# Q24brakelightsch.net
KiCad netlist of a schematic drawn in Altium Designer
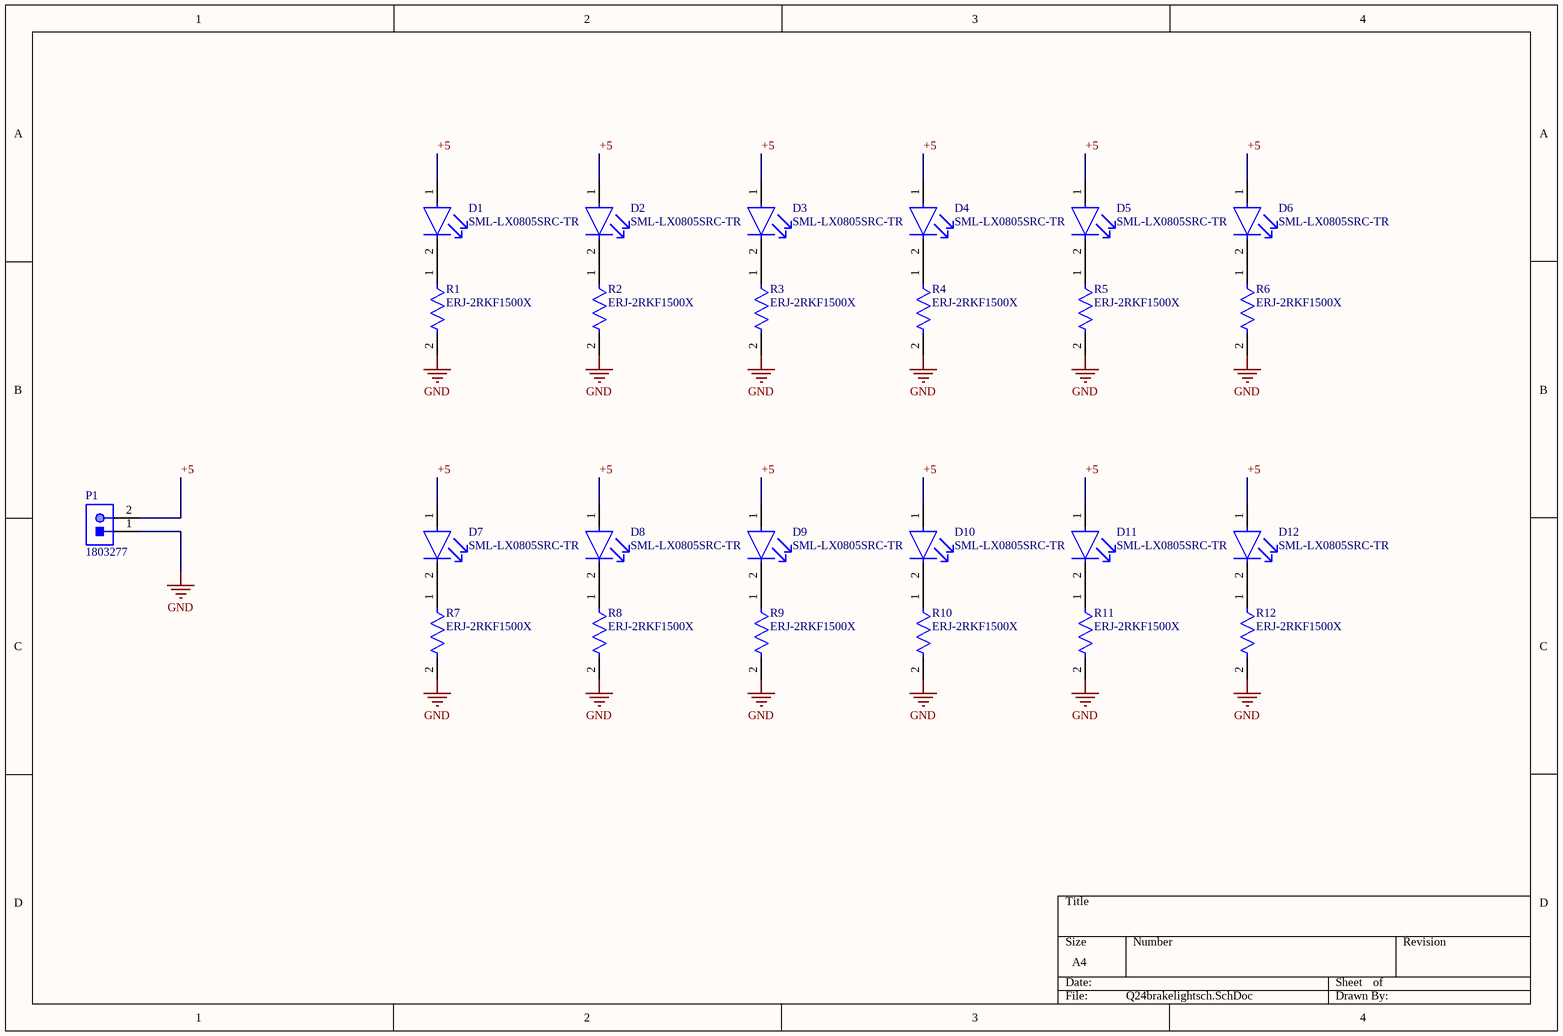
[diagram p0: Q24brakelightsch.SchDoc]

(export (version "E")
  (design (tool "Eeschema 10.0.6"))
  (components
    (comp (ref "D1")
      (value "SML-LX0805SRC-TR")
      (footprint "FP-SML-LX0805SRC-TR-MFG")
      (description "LED RED CLEAR SMD")
      (libsource (lib "Altium Content Vault") (part "ab1c01a81903e929fc6c44469aada92"))
    )
    (comp (ref "D2")
      (value "SML-LX0805SRC-TR")
      (footprint "FP-SML-LX0805SRC-TR-MFG")
      (description "LED RED CLEAR SMD")
      (libsource (lib "Altium Content Vault") (part "ab1c01a81903e929fc6c44469aada92"))
    )
    (comp (ref "D3")
      (value "SML-LX0805SRC-TR")
      (footprint "FP-SML-LX0805SRC-TR-MFG")
      (description "LED RED CLEAR SMD")
      (libsource (lib "Altium Content Vault") (part "ab1c01a81903e929fc6c44469aada92"))
    )
    (comp (ref "D4")
      (value "SML-LX0805SRC-TR")
      (footprint "FP-SML-LX0805SRC-TR-MFG")
      (description "LED RED CLEAR SMD")
      (libsource (lib "Altium Content Vault") (part "ab1c01a81903e929fc6c44469aada92"))
    )
    (comp (ref "D5")
      (value "SML-LX0805SRC-TR")
      (footprint "FP-SML-LX0805SRC-TR-MFG")
      (description "LED RED CLEAR SMD")
      (libsource (lib "Altium Content Vault") (part "ab1c01a81903e929fc6c44469aada92"))
    )
    (comp (ref "D6")
      (value "SML-LX0805SRC-TR")
      (footprint "FP-SML-LX0805SRC-TR-MFG")
      (description "LED RED CLEAR SMD")
      (libsource (lib "Altium Content Vault") (part "ab1c01a81903e929fc6c44469aada92"))
    )
    (comp (ref "D7")
      (value "SML-LX0805SRC-TR")
      (footprint "FP-SML-LX0805SRC-TR-MFG")
      (description "LED RED CLEAR SMD")
      (libsource (lib "Altium Content Vault") (part "ab1c01a81903e929fc6c44469aada92"))
    )
    (comp (ref "D8")
      (value "SML-LX0805SRC-TR")
      (footprint "FP-SML-LX0805SRC-TR-MFG")
      (description "LED RED CLEAR SMD")
      (libsource (lib "Altium Content Vault") (part "ab1c01a81903e929fc6c44469aada92"))
    )
    (comp (ref "D9")
      (value "SML-LX0805SRC-TR")
      (footprint "FP-SML-LX0805SRC-TR-MFG")
      (description "LED RED CLEAR SMD")
      (libsource (lib "Altium Content Vault") (part "ab1c01a81903e929fc6c44469aada92"))
    )
    (comp (ref "D10")
      (value "SML-LX0805SRC-TR")
      (footprint "FP-SML-LX0805SRC-TR-MFG")
      (description "LED RED CLEAR SMD")
      (libsource (lib "Altium Content Vault") (part "ab1c01a81903e929fc6c44469aada92"))
    )
    (comp (ref "D11")
      (value "SML-LX0805SRC-TR")
      (footprint "FP-SML-LX0805SRC-TR-MFG")
      (description "LED RED CLEAR SMD")
      (libsource (lib "Altium Content Vault") (part "ab1c01a81903e929fc6c44469aada92"))
    )
    (comp (ref "D12")
      (value "SML-LX0805SRC-TR")
      (footprint "FP-SML-LX0805SRC-TR-MFG")
      (description "LED RED CLEAR SMD")
      (libsource (lib "Altium Content Vault") (part "ab1c01a81903e929fc6c44469aada92"))
    )
    (comp (ref "P1")
      (value "1803277")
      (footprint "PHOE-1803277_V")
      (description "Male Header, Pitch 3.81 mm, 1 x 2 Position, Height 7.25 mm, Tail Length 3.4 mm, RoHS, Bulk")
      (fields (field (name "MANUFACTURER") "Phoenix Contact"))
      (libsource (lib "Americas- FSAE- Queens University") (part "CN-1P-M-R2"))
    )
    (comp (ref "R1")
      (value "ERJ-2RKF1500X")
      (footprint "FP-ERJ2RK-IPC_A")
      (description "RES SMD 150 OHM 1% 1/10W 0402")
      (fields (field (name "TOLERANCE") "1%"))
      (libsource (lib "Altium Content Vault") (part "1029c3af85768c4190bb7ad29bc67b5"))
    )
    (comp (ref "R2")
      (value "ERJ-2RKF1500X")
      (footprint "FP-ERJ2RK-IPC_A")
      (description "RES SMD 150 OHM 1% 1/10W 0402")
      (fields (field (name "TOLERANCE") "1%"))
      (libsource (lib "Altium Content Vault") (part "1029c3af85768c4190bb7ad29bc67b5"))
    )
    (comp (ref "R3")
      (value "ERJ-2RKF1500X")
      (footprint "FP-ERJ2RK-IPC_A")
      (description "RES SMD 150 OHM 1% 1/10W 0402")
      (fields (field (name "TOLERANCE") "1%"))
      (libsource (lib "Altium Content Vault") (part "1029c3af85768c4190bb7ad29bc67b5"))
    )
    (comp (ref "R4")
      (value "ERJ-2RKF1500X")
      (footprint "FP-ERJ2RK-IPC_A")
      (description "RES SMD 150 OHM 1% 1/10W 0402")
      (fields (field (name "TOLERANCE") "1%"))
      (libsource (lib "Altium Content Vault") (part "1029c3af85768c4190bb7ad29bc67b5"))
    )
    (comp (ref "R5")
      (value "ERJ-2RKF1500X")
      (footprint "FP-ERJ2RK-IPC_A")
      (description "RES SMD 150 OHM 1% 1/10W 0402")
      (fields (field (name "TOLERANCE") "1%"))
      (libsource (lib "Altium Content Vault") (part "1029c3af85768c4190bb7ad29bc67b5"))
    )
    (comp (ref "R6")
      (value "ERJ-2RKF1500X")
      (footprint "FP-ERJ2RK-IPC_A")
      (description "RES SMD 150 OHM 1% 1/10W 0402")
      (fields (field (name "TOLERANCE") "1%"))
      (libsource (lib "Altium Content Vault") (part "1029c3af85768c4190bb7ad29bc67b5"))
    )
    (comp (ref "R7")
      (value "ERJ-2RKF1500X")
      (footprint "FP-ERJ2RK-IPC_A")
      (description "RES SMD 150 OHM 1% 1/10W 0402")
      (fields (field (name "TOLERANCE") "1%"))
      (libsource (lib "Altium Content Vault") (part "1029c3af85768c4190bb7ad29bc67b5"))
    )
    (comp (ref "R8")
      (value "ERJ-2RKF1500X")
      (footprint "FP-ERJ2RK-IPC_A")
      (description "RES SMD 150 OHM 1% 1/10W 0402")
      (fields (field (name "TOLERANCE") "1%"))
      (libsource (lib "Altium Content Vault") (part "1029c3af85768c4190bb7ad29bc67b5"))
    )
    (comp (ref "R9")
      (value "ERJ-2RKF1500X")
      (footprint "FP-ERJ2RK-IPC_A")
      (description "RES SMD 150 OHM 1% 1/10W 0402")
      (fields (field (name "TOLERANCE") "1%"))
      (libsource (lib "Altium Content Vault") (part "1029c3af85768c4190bb7ad29bc67b5"))
    )
    (comp (ref "R10")
      (value "ERJ-2RKF1500X")
      (footprint "FP-ERJ2RK-IPC_A")
      (description "RES SMD 150 OHM 1% 1/10W 0402")
      (fields (field (name "TOLERANCE") "1%"))
      (libsource (lib "Altium Content Vault") (part "1029c3af85768c4190bb7ad29bc67b5"))
    )
    (comp (ref "R11")
      (value "ERJ-2RKF1500X")
      (footprint "FP-ERJ2RK-IPC_A")
      (description "RES SMD 150 OHM 1% 1/10W 0402")
      (fields (field (name "TOLERANCE") "1%"))
      (libsource (lib "Altium Content Vault") (part "1029c3af85768c4190bb7ad29bc67b5"))
    )
    (comp (ref "R12")
      (value "ERJ-2RKF1500X")
      (footprint "FP-ERJ2RK-IPC_A")
      (description "RES SMD 150 OHM 1% 1/10W 0402")
      (fields (field (name "TOLERANCE") "1%"))
      (libsource (lib "Altium Content Vault") (part "1029c3af85768c4190bb7ad29bc67b5"))
    )
  )
  (nets
    (net (code "1") (name "/+5") (class "Default")
      (node (ref "D1") (pin "1") (pinfunction "A_1") (pintype "passive"))
      (node (ref "D10") (pin "1") (pinfunction "A_1") (pintype "passive"))
      (node (ref "D11") (pin "1") (pinfunction "A_1") (pintype "passive"))
      (node (ref "D12") (pin "1") (pinfunction "A_1") (pintype "passive"))
      (node (ref "D2") (pin "1") (pinfunction "A_1") (pintype "passive"))
      (node (ref "D3") (pin "1") (pinfunction "A_1") (pintype "passive"))
      (node (ref "D4") (pin "1") (pinfunction "A_1") (pintype "passive"))
      (node (ref "D5") (pin "1") (pinfunction "A_1") (pintype "passive"))
      (node (ref "D6") (pin "1") (pinfunction "A_1") (pintype "passive"))
      (node (ref "D7") (pin "1") (pinfunction "A_1") (pintype "passive"))
      (node (ref "D8") (pin "1") (pinfunction "A_1") (pintype "passive"))
      (node (ref "D9") (pin "1") (pinfunction "A_1") (pintype "passive"))
      (node (ref "P1") (pin "2") (pinfunction "2_2") (pintype "passive"))
    )
    (net (code "2") (name "GND") (class "Default")
      (node (ref "P1") (pin "1") (pinfunction "1_1") (pintype "passive"))
      (node (ref "R1") (pin "2") (pinfunction "2_2") (pintype "passive"))
      (node (ref "R10") (pin "2") (pinfunction "2_2") (pintype "passive"))
      (node (ref "R11") (pin "2") (pinfunction "2_2") (pintype "passive"))
      (node (ref "R12") (pin "2") (pinfunction "2_2") (pintype "passive"))
      (node (ref "R2") (pin "2") (pinfunction "2_2") (pintype "passive"))
      (node (ref "R3") (pin "2") (pinfunction "2_2") (pintype "passive"))
      (node (ref "R4") (pin "2") (pinfunction "2_2") (pintype "passive"))
      (node (ref "R5") (pin "2") (pinfunction "2_2") (pintype "passive"))
      (node (ref "R6") (pin "2") (pinfunction "2_2") (pintype "passive"))
      (node (ref "R7") (pin "2") (pinfunction "2_2") (pintype "passive"))
      (node (ref "R8") (pin "2") (pinfunction "2_2") (pintype "passive"))
      (node (ref "R9") (pin "2") (pinfunction "2_2") (pintype "passive"))
    )
    (net (code "3") (name "Net-(D1-C)") (class "Default")
      (node (ref "D1") (pin "2") (pinfunction "C_2") (pintype "passive"))
      (node (ref "R1") (pin "1") (pinfunction "1_1") (pintype "passive"))
    )
    (net (code "4") (name "Net-(D2-C)") (class "Default")
      (node (ref "D2") (pin "2") (pinfunction "C_2") (pintype "passive"))
      (node (ref "R2") (pin "1") (pinfunction "1_1") (pintype "passive"))
    )
    (net (code "5") (name "Net-(D3-C)") (class "Default")
      (node (ref "D3") (pin "2") (pinfunction "C_2") (pintype "passive"))
      (node (ref "R3") (pin "1") (pinfunction "1_1") (pintype "passive"))
    )
    (net (code "6") (name "Net-(D4-C)") (class "Default")
      (node (ref "D4") (pin "2") (pinfunction "C_2") (pintype "passive"))
      (node (ref "R4") (pin "1") (pinfunction "1_1") (pintype "passive"))
    )
    (net (code "7") (name "Net-(D5-C)") (class "Default")
      (node (ref "D5") (pin "2") (pinfunction "C_2") (pintype "passive"))
      (node (ref "R5") (pin "1") (pinfunction "1_1") (pintype "passive"))
    )
    (net (code "8") (name "Net-(D6-C)") (class "Default")
      (node (ref "D6") (pin "2") (pinfunction "C_2") (pintype "passive"))
      (node (ref "R6") (pin "1") (pinfunction "1_1") (pintype "passive"))
    )
    (net (code "9") (name "Net-(D7-C)") (class "Default")
      (node (ref "D7") (pin "2") (pinfunction "C_2") (pintype "passive"))
      (node (ref "R7") (pin "1") (pinfunction "1_1") (pintype "passive"))
    )
    (net (code "10") (name "Net-(D8-C)") (class "Default")
      (node (ref "D8") (pin "2") (pinfunction "C_2") (pintype "passive"))
      (node (ref "R8") (pin "1") (pinfunction "1_1") (pintype "passive"))
    )
    (net (code "11") (name "Net-(D9-C)") (class "Default")
      (node (ref "D9") (pin "2") (pinfunction "C_2") (pintype "passive"))
      (node (ref "R9") (pin "1") (pinfunction "1_1") (pintype "passive"))
    )
    (net (code "12") (name "Net-(D10-C)") (class "Default")
      (node (ref "D10") (pin "2") (pinfunction "C_2") (pintype "passive"))
      (node (ref "R10") (pin "1") (pinfunction "1_1") (pintype "passive"))
    )
    (net (code "13") (name "Net-(D11-C)") (class "Default")
      (node (ref "D11") (pin "2") (pinfunction "C_2") (pintype "passive"))
      (node (ref "R11") (pin "1") (pinfunction "1_1") (pintype "passive"))
    )
    (net (code "14") (name "Net-(D12-C)") (class "Default")
      (node (ref "D12") (pin "2") (pinfunction "C_2") (pintype "passive"))
      (node (ref "R12") (pin "1") (pinfunction "1_1") (pintype "passive"))
    )
  )
)
